# 1_IOT_ON_OFF_220V_LDR.net
KiCad netlist of a schematic drawn in EAGLE
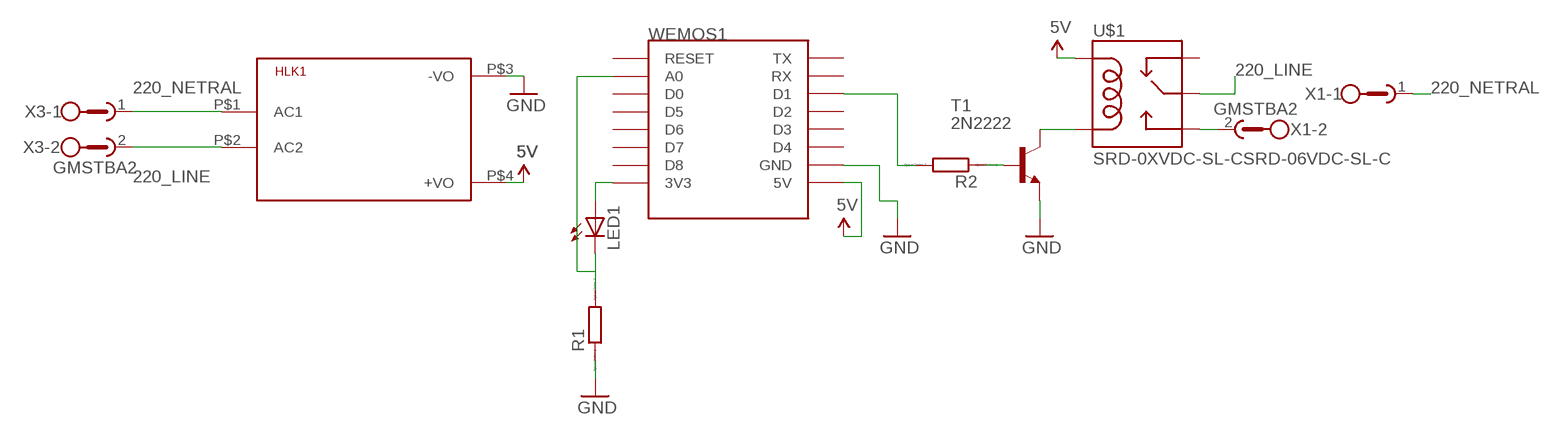
[diagram p0: schematic, sheet 1]

(export (version "E")
  (design (tool "Eeschema 10.0.6"))
  (components
    (comp (ref "HLK1")
      (value "HLK-PM013W")
      (footprint "eagle-import:HLK-PM01")
      (libsource (lib "eagle-import") (part "HLK-PM013W"))
    )
    (comp (ref "LED1")
      (value "LED5MM")
      (footprint "eagle-import:LED5MM")
      (libsource (lib "eagle-import") (part "LED5MM"))
    )
    (comp (ref "R1")
      (value "R-EU_0207_10")
      (footprint "eagle-import:0207_10")
      (libsource (lib "eagle-import") (part "R-EU_0207_10"))
    )
    (comp (ref "R2")
      (value "R-EU_0207_10")
      (footprint "eagle-import:0207_10")
      (libsource (lib "eagle-import") (part "R-EU_0207_10"))
    )
    (comp (ref "T1")
      (value "2N2222")
      (footprint "eagle-import:TO18")
      (libsource (lib "eagle-import") (part "2N2222"))
    )
    (comp (ref "U$1")
      (value "SRD-0XVDC-SL-CSRD-06VDC-SL-C")
      (footprint "eagle-import:SRD-0XVDC-SL-C")
      (libsource (lib "eagle-import") (part "SRD-0XVDC-SL-CSRD-06VDC-SL-C"))
    )
    (comp (ref "WEMOS1")
      (value "WEMOS-D1-MINI")
      (footprint "eagle-import:WEMOS-D1-MINI")
      (libsource (lib "eagle-import") (part "WEMOS-D1-MINI"))
    )
    (comp (ref "X1")
      (value "GMSTBA2")
      (footprint "eagle-import:GMSTBA2")
      (fields (field (name "MF") "FARNELL") (field (name "MPN") "1757242"))
      (libsource (lib "eagle-import") (part "GMSTBA2"))
    )
    (comp (ref "X3")
      (value "GMSTBA2")
      (footprint "eagle-import:GMSTBA2")
      (fields (field (name "MF") "FARNELL") (field (name "MPN") "1757242"))
      (libsource (lib "eagle-import") (part "GMSTBA2"))
    )
  )
  (nets
    (net (code "1") (name "/220_LINE") (class "Default")
      (node (ref "HLK1") (pin "P$2") (pinfunction "AC2_P$2") (pintype "bidirectional"))
      (node (ref "U$1") (pin "SWCOMMON") (pinfunction "SWCOMMON_SWCOMMON") (pintype "bidirectional"))
      (node (ref "X3") (pin "2") (pinfunction "1_2") (pintype "passive"))
    )
    (net (code "2") (name "/220_NETRAL") (class "Default")
      (node (ref "HLK1") (pin "P$1") (pinfunction "AC1_P$1") (pintype "bidirectional"))
      (node (ref "X1") (pin "1") (pinfunction "1_1") (pintype "passive"))
      (node (ref "X3") (pin "1") (pinfunction "1_1") (pintype "passive"))
    )
    (net (code "3") (name "5V") (class "Default")
      (node (ref "HLK1") (pin "P$4") (pinfunction "+VO_P$4") (pintype "bidirectional"))
      (node (ref "U$1") (pin "COIL1") (pinfunction "COIL1_COIL1") (pintype "bidirectional"))
      (node (ref "WEMOS1") (pin "5V") (pinfunction "5V_5V") (pintype "bidirectional"))
    )
    (net (code "4") (name "GND") (class "Default")
      (node (ref "HLK1") (pin "P$3") (pinfunction "-VO_P$3") (pintype "bidirectional"))
      (node (ref "R1") (pin "1") (pinfunction "1_1") (pintype "passive"))
      (node (ref "T1") (pin "1") (pinfunction "E_1") (pintype "passive"))
      (node (ref "WEMOS1") (pin "GND") (pinfunction "GND_GND") (pintype "bidirectional"))
    )
    (net (code "5") (name "Net-(LED1-C)") (class "Default")
      (node (ref "LED1") (pin "K") (pinfunction "C_K") (pintype "passive"))
      (node (ref "R1") (pin "2") (pinfunction "2_2") (pintype "passive"))
      (node (ref "WEMOS1") (pin "A0") (pinfunction "A0_A0") (pintype "bidirectional"))
    )
    (net (code "6") (name "Net-(LED1-PadA)") (class "Default")
      (node (ref "LED1") (pin "A") (pinfunction "A_A") (pintype "passive"))
      (node (ref "WEMOS1") (pin "3V3") (pinfunction "3V3_3V3") (pintype "bidirectional"))
    )
    (net (code "7") (name "Net-(R2-Pad2)") (class "Default")
      (node (ref "R2") (pin "2") (pinfunction "2_2") (pintype "passive"))
      (node (ref "WEMOS1") (pin "D1") (pinfunction "D1_D1") (pintype "bidirectional"))
    )
    (net (code "8") (name "Net-(T1-B)") (class "Default")
      (node (ref "R2") (pin "1") (pinfunction "1_1") (pintype "passive"))
      (node (ref "T1") (pin "2") (pinfunction "B_2") (pintype "passive"))
    )
    (net (code "9") (name "Net-(T1-C)") (class "Default")
      (node (ref "T1") (pin "3") (pinfunction "C_3") (pintype "passive"))
      (node (ref "U$1") (pin "COIL0") (pinfunction "COIL0_COIL0") (pintype "bidirectional"))
    )
    (net (code "10") (name "Net-(X1B-1)") (class "Default")
      (node (ref "U$1") (pin "SWOPEN") (pinfunction "SWOPEN_SWOPEN") (pintype "bidirectional"))
      (node (ref "X1") (pin "2") (pinfunction "1_2") (pintype "passive"))
    )
    (net (code "11") (name "unconnected-(U$1-SWCLOSE-PadSWCLOSED)") (class "Default")
      (node (ref "U$1") (pin "SWCLOSED") (pinfunction "SWCLOSE_SWCLOSED") (pintype "bidirectional"))
    )
    (net (code "12") (name "unconnected-(WEMOS1-PadD0)") (class "Default")
      (node (ref "WEMOS1") (pin "D0") (pinfunction "D0_D0") (pintype "bidirectional"))
    )
    (net (code "13") (name "unconnected-(WEMOS1-PadD2)") (class "Default")
      (node (ref "WEMOS1") (pin "D2") (pinfunction "D2_D2") (pintype "bidirectional"))
    )
    (net (code "14") (name "unconnected-(WEMOS1-PadD3)") (class "Default")
      (node (ref "WEMOS1") (pin "D3") (pinfunction "D3_D3") (pintype "bidirectional"))
    )
    (net (code "15") (name "unconnected-(WEMOS1-PadD4)") (class "Default")
      (node (ref "WEMOS1") (pin "D4") (pinfunction "D4_D4") (pintype "bidirectional"))
    )
    (net (code "16") (name "unconnected-(WEMOS1-PadD5)") (class "Default")
      (node (ref "WEMOS1") (pin "D5") (pinfunction "D5_D5") (pintype "bidirectional"))
    )
    (net (code "17") (name "unconnected-(WEMOS1-PadD6)") (class "Default")
      (node (ref "WEMOS1") (pin "D6") (pinfunction "D6_D6") (pintype "bidirectional"))
    )
    (net (code "18") (name "unconnected-(WEMOS1-PadD7)") (class "Default")
      (node (ref "WEMOS1") (pin "D7") (pinfunction "D7_D7") (pintype "bidirectional"))
    )
    (net (code "19") (name "unconnected-(WEMOS1-PadD8)") (class "Default")
      (node (ref "WEMOS1") (pin "D8") (pinfunction "D8_D8") (pintype "bidirectional"))
    )
    (net (code "20") (name "unconnected-(WEMOS1-PadRESET)") (class "Default")
      (node (ref "WEMOS1") (pin "RESET") (pinfunction "RESET_RESET") (pintype "bidirectional"))
    )
    (net (code "21") (name "unconnected-(WEMOS1-PadRX)") (class "Default")
      (node (ref "WEMOS1") (pin "RX") (pinfunction "RX_RX") (pintype "bidirectional"))
    )
    (net (code "22") (name "unconnected-(WEMOS1-PadTX)") (class "Default")
      (node (ref "WEMOS1") (pin "TX") (pinfunction "TX_TX") (pintype "bidirectional"))
    )
  )
)
